# 4_USB_TO_UART.net
KiCad netlist of a schematic drawn in Altium Designer
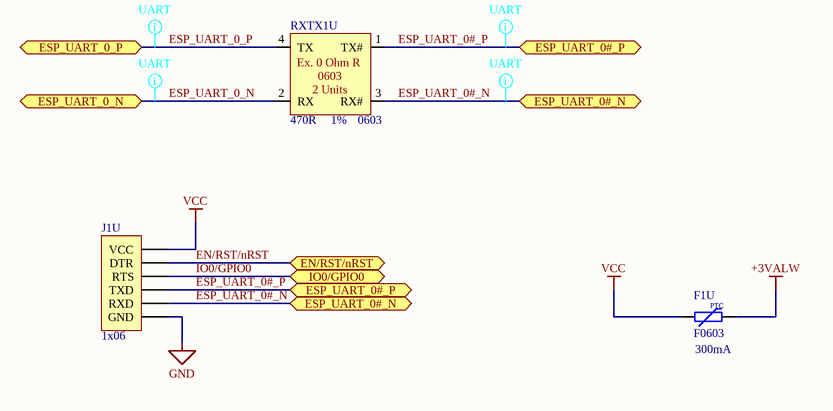
[diagram p0: 4_USB_TO_UART.SchDoc]

(export (version "E")
  (design (tool "Eeschema 10.0.6"))
  (components
    (comp (ref "F1U")
      (value "F0603")
      (footprint "R0603-IPC_C")
      (description "Fuse PPTC SMD 0603")
      (fields (field (name "ALTIUM_VALUE") "300mA"))
      (libsource (lib "Lib_Fuse") (part "FUSE_PPTC_0603"))
    )
    (comp (ref "J1U")
      (value "1x06")
      (footprint "PinHeader_1x06_P2.54mm_Vertical_No_3D")
      (libsource (lib "Lib_Connector_PinHeader_2.54mm") (part "UART_1X06_P2.54mm_2"))
    )
    (comp (ref "RXTX1U")
      (value "470R")
      (footprint "UART_TX_RX_0603")
      (description "UART RX/TX Pokayoke")
      (fields (field (name "TOL") "1%") (field (name "PACKAGE") "0603") (field (name "Comment") "UART_TX_RX"))
      (libsource (lib "Lib_UART_TX_RX_Jumper") (part "UART_TX_RX_0603"))
    )
  )
  (nets
    (net (code "1") (name "+3VALW") (class "Default")
      (node (ref "F1U") (pin "2") (pinfunction "2_2") (pintype "passive"))
    )
    (net (code "2") (name "/EN{slash}RST{slash}nRST") (class "Default")
      (node (ref "J1U") (pin "5") (pinfunction "DTR_5") (pintype "passive"))
    )
    (net (code "3") (name "/ESP_UART_0#_N") (class "Default")
      (node (ref "J1U") (pin "2") (pinfunction "RXD_2") (pintype "passive"))
      (node (ref "RXTX1U") (pin "3") (pinfunction "RX#_3") (pintype "passive"))
    )
    (net (code "4") (name "/ESP_UART_0#_P") (class "Default")
      (node (ref "J1U") (pin "3") (pinfunction "TXD_3") (pintype "passive"))
      (node (ref "RXTX1U") (pin "1") (pinfunction "TX#_1") (pintype "passive"))
    )
    (net (code "5") (name "/ESP_UART_0_N") (class "Default")
      (node (ref "RXTX1U") (pin "2") (pinfunction "RX_2") (pintype "passive"))
    )
    (net (code "6") (name "/ESP_UART_0_P") (class "Default")
      (node (ref "RXTX1U") (pin "4") (pinfunction "TX_4") (pintype "passive"))
    )
    (net (code "7") (name "/IO0{slash}GPIO0") (class "Default")
      (node (ref "J1U") (pin "4") (pinfunction "RTS_4") (pintype "passive"))
    )
    (net (code "8") (name "GND") (class "Default")
      (node (ref "J1U") (pin "1") (pinfunction "GND_1") (pintype "passive"))
    )
    (net (code "9") (name "VCC") (class "Default")
      (node (ref "F1U") (pin "1") (pinfunction "1_1") (pintype "passive"))
      (node (ref "J1U") (pin "6") (pinfunction "VCC_6") (pintype "passive"))
    )
  )
)
